# ANGEL_II_Type_III_ver2.net
KiCad netlist of a schematic drawn in EAGLE
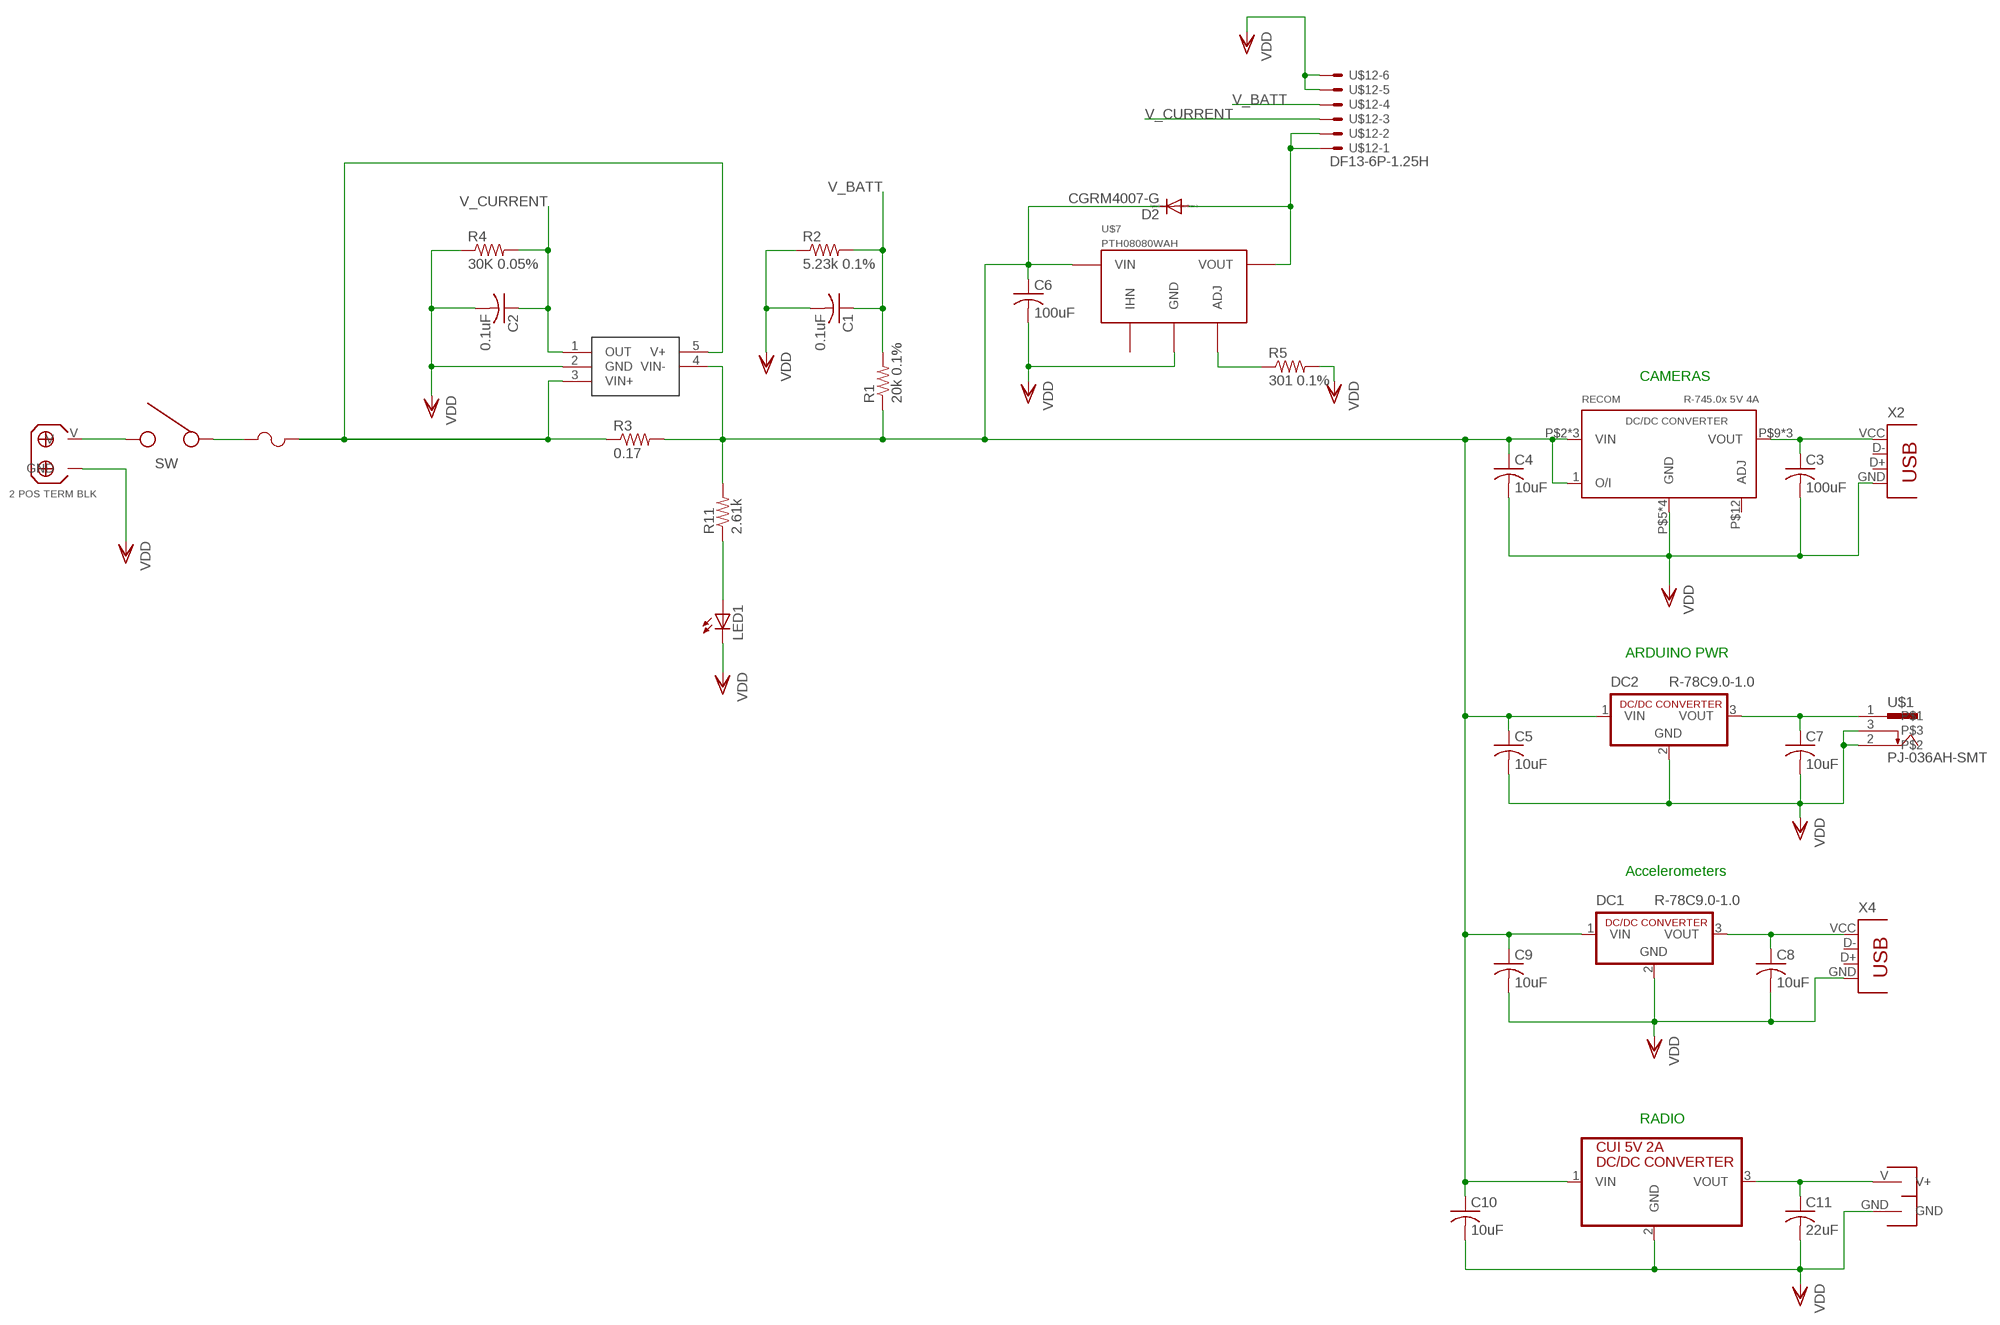
[diagram p0: schematic, sheet 1]

(export (version "E")
  (design (tool "Eeschema 10.0.6"))
  (components
    (comp (ref "C1")
      (value "0.1uF")
      (footprint "eagle-import:C0603")
      (libsource (lib "eagle-import") (part "C-USC0603"))
    )
    (comp (ref "C2")
      (value "0.1uF")
      (footprint "eagle-import:C0603")
      (libsource (lib "eagle-import") (part "C-USC0603"))
    )
    (comp (ref "C3")
      (value "100uF")
      (footprint "eagle-import:C1210")
      (libsource (lib "eagle-import") (part "C-USC1210"))
    )
    (comp (ref "C4")
      (value "10uF")
      (footprint "eagle-import:C1206")
      (libsource (lib "eagle-import") (part "C-USC1206"))
    )
    (comp (ref "C5")
      (value "10uF")
      (footprint "eagle-import:C1206")
      (libsource (lib "eagle-import") (part "C-USC1206"))
    )
    (comp (ref "C6")
      (value "100uF")
      (footprint "eagle-import:C1210")
      (libsource (lib "eagle-import") (part "C-USC1210"))
    )
    (comp (ref "C7")
      (value "10uF")
      (footprint "eagle-import:C1206")
      (libsource (lib "eagle-import") (part "C-USC1206"))
    )
    (comp (ref "C8")
      (value "10uF")
      (footprint "eagle-import:C1206")
      (libsource (lib "eagle-import") (part "C-USC1206"))
    )
    (comp (ref "C9")
      (value "10uF")
      (footprint "eagle-import:C1206")
      (libsource (lib "eagle-import") (part "C-USC1206"))
    )
    (comp (ref "C10")
      (value "10uF")
      (footprint "eagle-import:C1206")
      (libsource (lib "eagle-import") (part "C-USC1206"))
    )
    (comp (ref "C11")
      (value "22uF")
      (footprint "eagle-import:C1210")
      (libsource (lib "eagle-import") (part "C-USC1210"))
    )
    (comp (ref "D2")
      (value "CGRM4007-G")
      (footprint "eagle-import:SOD-123_MINI-SMA")
      (libsource (lib "eagle-import") (part "CGRM400-G7"))
    )
    (comp (ref "DC1")
      (value "R-78C9.0-1.0")
      (footprint "eagle-import:SIP3")
      (libsource (lib "eagle-import") (part "R-78C-1.09.0"))
    )
    (comp (ref "DC2")
      (value "R-78C9.0-1.0")
      (footprint "eagle-import:SIP3")
      (libsource (lib "eagle-import") (part "R-78C-1.09.0"))
    )
    (comp (ref "LED1")
      (value "LEDCHIPLED_0603")
      (footprint "eagle-import:CHIPLED_0603")
      (libsource (lib "eagle-import") (part "LEDCHIPLED_0603"))
    )
    (comp (ref "R1")
      (value "20k 0.1%")
      (footprint "eagle-import:R0603")
      (libsource (lib "eagle-import") (part "R-US_R0603"))
    )
    (comp (ref "R2")
      (value "5.23k 0.1%")
      (footprint "eagle-import:R0805")
      (libsource (lib "eagle-import") (part "R-US_R0805"))
    )
    (comp (ref "R3")
      (value "0.17")
      (footprint "eagle-import:R2512")
      (libsource (lib "eagle-import") (part "R-US_R2512"))
    )
    (comp (ref "R4")
      (value "30K 0.05%")
      (footprint "eagle-import:R0603")
      (libsource (lib "eagle-import") (part "R-US_R0603"))
    )
    (comp (ref "R5")
      (value "301 0.1%")
      (footprint "eagle-import:R0805")
      (libsource (lib "eagle-import") (part "R-US_R0805"))
    )
    (comp (ref "R11")
      (value "2.61k")
      (footprint "eagle-import:R0805")
      (libsource (lib "eagle-import") (part "R-US_R0805"))
    )
    (comp (ref "U$1")
      (value "PJ-036AH-SMT")
      (footprint "eagle-import:SMT_DC_POWERJACK")
      (libsource (lib "eagle-import") (part "PJ-036AH-SMT"))
    )
    (comp (ref "U$2")
      (value "INA169")
      (footprint "eagle-import:SOT23-5")
      (libsource (lib "eagle-import") (part "INA169"))
    )
    (comp (ref "U$5")
      (value "CUI_DCDC_5V2A")
      (footprint "eagle-import:CUI_V200_DCDC")
      (libsource (lib "eagle-import") (part "CUI_DCDC_5V2A"))
    )
    (comp (ref "U$6")
      (value "SPST_ROCKER_SW")
      (footprint "eagle-import:ROCKER_SW_SPST")
      (libsource (lib "eagle-import") (part "SPST_ROCKER_SW"))
    )
    (comp (ref "U$7")
      (value "PTH08080WAH")
      (footprint "eagle-import:PTH08080W_TH")
      (libsource (lib "eagle-import") (part "PTH08080WAH"))
    )
    (comp (ref "U$9")
      (value "MOLEX_2POS_HEADRE_TB")
      (footprint "eagle-import:TERM_BLK_HDR_2POS_VERT_3P5MM")
      (libsource (lib "eagle-import") (part "MOLEX_2POS_HEADRE_TB"))
    )
    (comp (ref "U$10")
      (value "2POS_TB_3.81MM")
      (footprint "eagle-import:2POS_TB_3P81MM")
      (libsource (lib "eagle-import") (part "2POS_TB_3.81MM"))
    )
    (comp (ref "U$11")
      (value "LITTLEFUSE_1206SMT")
      (footprint "eagle-import:LITTLEFUSE_SMT")
      (libsource (lib "eagle-import") (part "LITTLEFUSE_1206SMT"))
    )
    (comp (ref "U$12")
      (value "DF13-6P-1.25H")
      (footprint "eagle-import:DF13A-6P-1.25H")
      (libsource (lib "eagle-import") (part "DF13-6P-1.25?H"))
    )
    (comp (ref "U$13")
      (value "RECOM_R745_5V4A_DCDC")
      (footprint "eagle-import:12SIP_PIN")
      (libsource (lib "eagle-import") (part "RECOM_R745_5V4A_DCDC"))
    )
    (comp (ref "X2")
      (value "87583-2010BLF")
      (footprint "eagle-import:USB-A_87583-2010BLF")
      (libsource (lib "eagle-import") (part "87583-2010BLF"))
    )
    (comp (ref "X4")
      (value "87583-2010BLF")
      (footprint "eagle-import:USB-A_87583-2010BLF")
      (libsource (lib "eagle-import") (part "87583-2010BLF"))
    )
  )
  (nets
    (net (code "1") (name "/V_BATT") (class "Default")
      (node (ref "C1") (pin "1") (pinfunction "1_1") (pintype "passive"))
      (node (ref "R1") (pin "2") (pinfunction "2_2") (pintype "passive"))
      (node (ref "R2") (pin "2") (pinfunction "2_2") (pintype "passive"))
      (node (ref "U$12") (pin "4") (pinfunction "S_4") (pintype "passive"))
    )
    (net (code "2") (name "/V_CURRENT") (class "Default")
      (node (ref "C2") (pin "1") (pinfunction "1_1") (pintype "passive"))
      (node (ref "R4") (pin "2") (pinfunction "2_2") (pintype "passive"))
      (node (ref "U$12") (pin "3") (pinfunction "S_3") (pintype "passive"))
      (node (ref "U$2") (pin "1") (pinfunction "OUT_1") (pintype "bidirectional"))
    )
    (net (code "3") (name "Net-(DC1-VIN)") (class "Default")
      (node (ref "C10") (pin "1") (pinfunction "1_1") (pintype "passive"))
      (node (ref "C4") (pin "1") (pinfunction "1_1") (pintype "passive"))
      (node (ref "C5") (pin "1") (pinfunction "1_1") (pintype "passive"))
      (node (ref "C6") (pin "1") (pinfunction "1_1") (pintype "passive"))
      (node (ref "C9") (pin "1") (pinfunction "1_1") (pintype "passive"))
      (node (ref "D2") (pin "C") (pinfunction "C_C") (pintype "passive"))
      (node (ref "DC1") (pin "1") (pinfunction "VIN_1") (pintype "passive"))
      (node (ref "DC2") (pin "1") (pinfunction "VIN_1") (pintype "passive"))
      (node (ref "R1") (pin "1") (pinfunction "1_1") (pintype "passive"))
      (node (ref "R11") (pin "2") (pinfunction "2_2") (pintype "passive"))
      (node (ref "R3") (pin "2") (pinfunction "2_2") (pintype "passive"))
      (node (ref "U$13") (pin "1") (pinfunction "O/I_1") (pintype "bidirectional"))
      (node (ref "U$13") (pin "P$2") (pinfunction "VIN_P$2") (pintype "bidirectional"))
      (node (ref "U$13") (pin "P$3") (pinfunction "VIN_P$3") (pintype "bidirectional"))
      (node (ref "U$13") (pin "P$4") (pinfunction "VIN_P$4") (pintype "bidirectional"))
      (node (ref "U$2") (pin "4") (pinfunction "VIN-_4") (pintype "bidirectional"))
      (node (ref "U$5") (pin "1") (pinfunction "VIN_1") (pintype "bidirectional"))
      (node (ref "U$7") (pin "1") (pinfunction "VIN_1") (pintype "power_in"))
    )
    (net (code "4") (name "Net-(DC1-VOUT)") (class "Default")
      (node (ref "C8") (pin "1") (pinfunction "1_1") (pintype "passive"))
      (node (ref "DC1") (pin "3") (pinfunction "VOUT_3") (pintype "passive"))
      (node (ref "X4") (pin "VCC") (pinfunction "1_VCC") (pintype "passive"))
    )
    (net (code "5") (name "Net-(DC2-VOUT)") (class "Default")
      (node (ref "C7") (pin "1") (pinfunction "1_1") (pintype "passive"))
      (node (ref "DC2") (pin "3") (pinfunction "VOUT_3") (pintype "passive"))
      (node (ref "U$1") (pin "1") (pinfunction "P$1_1") (pintype "bidirectional"))
    )
    (net (code "6") (name "Net-(LED1-PadA)") (class "Default")
      (node (ref "LED1") (pin "A") (pinfunction "A_A") (pintype "passive"))
      (node (ref "R11") (pin "1") (pinfunction "1_1") (pintype "passive"))
    )
    (net (code "7") (name "Net-(U$5-VOUT)") (class "Default")
      (node (ref "C11") (pin "1") (pinfunction "1_1") (pintype "passive"))
      (node (ref "U$5") (pin "3") (pinfunction "VOUT_3") (pintype "bidirectional"))
      (node (ref "U$9") (pin "V") (pinfunction "V+_V") (pintype "bidirectional"))
    )
    (net (code "8") (name "Net-(U$6-1)") (class "Default")
      (node (ref "U$10") (pin "V") (pinfunction "V_V") (pintype "bidirectional"))
      (node (ref "U$6") (pin "P$1") (pinfunction "1_P$1") (pintype "bidirectional"))
    )
    (net (code "9") (name "Net-(U$7-ADJ)") (class "Default")
      (node (ref "R5") (pin "1") (pinfunction "1_1") (pintype "passive"))
      (node (ref "U$7") (pin "4") (pinfunction "ADJ_4") (pintype "bidirectional"))
    )
    (net (code "10") (name "Net-(U$11-P$2)") (class "Default")
      (node (ref "R3") (pin "1") (pinfunction "1_1") (pintype "passive"))
      (node (ref "U$11") (pin "P$3") (pinfunction "P$2_P$3") (pintype "bidirectional"))
      (node (ref "U$2") (pin "3") (pinfunction "VIN+_3") (pintype "bidirectional"))
      (node (ref "U$2") (pin "5") (pinfunction "V+_5") (pintype "bidirectional"))
    )
    (net (code "11") (name "Net-(U$11-PadP$1)") (class "Default")
      (node (ref "U$11") (pin "P$1") (pinfunction "P$1_P$1") (pintype "bidirectional"))
      (node (ref "U$6") (pin "P$2") (pinfunction "P$2_P$2") (pintype "bidirectional"))
    )
    (net (code "12") (name "Net-(U$12A-S)") (class "Default")
      (node (ref "D2") (pin "A") (pinfunction "A_A") (pintype "passive"))
      (node (ref "U$12") (pin "1") (pinfunction "S_1") (pintype "passive"))
      (node (ref "U$12") (pin "2") (pinfunction "S_2") (pintype "passive"))
      (node (ref "U$7") (pin "3") (pinfunction "VOUT_3") (pintype "power_in"))
    )
    (net (code "13") (name "Net-(X2-1)") (class "Default")
      (node (ref "C3") (pin "1") (pinfunction "1_1") (pintype "passive"))
      (node (ref "U$13") (pin "P$10") (pinfunction "VOUT_P$10") (pintype "bidirectional"))
      (node (ref "U$13") (pin "P$11") (pinfunction "VOUT_P$11") (pintype "bidirectional"))
      (node (ref "U$13") (pin "P$9") (pinfunction "VOUT_P$9") (pintype "bidirectional"))
      (node (ref "X2") (pin "VCC") (pinfunction "1_VCC") (pintype "passive"))
    )
    (net (code "14") (name "VDD") (class "Default")
      (node (ref "C1") (pin "2") (pinfunction "2_2") (pintype "passive"))
      (node (ref "C10") (pin "2") (pinfunction "2_2") (pintype "passive"))
      (node (ref "C11") (pin "2") (pinfunction "2_2") (pintype "passive"))
      (node (ref "C2") (pin "2") (pinfunction "2_2") (pintype "passive"))
      (node (ref "C3") (pin "2") (pinfunction "2_2") (pintype "passive"))
      (node (ref "C4") (pin "2") (pinfunction "2_2") (pintype "passive"))
      (node (ref "C5") (pin "2") (pinfunction "2_2") (pintype "passive"))
      (node (ref "C6") (pin "2") (pinfunction "2_2") (pintype "passive"))
      (node (ref "C7") (pin "2") (pinfunction "2_2") (pintype "passive"))
      (node (ref "C8") (pin "2") (pinfunction "2_2") (pintype "passive"))
      (node (ref "C9") (pin "2") (pinfunction "2_2") (pintype "passive"))
      (node (ref "DC1") (pin "2") (pinfunction "GND_2") (pintype "passive"))
      (node (ref "DC2") (pin "2") (pinfunction "GND_2") (pintype "passive"))
      (node (ref "LED1") (pin "C") (pinfunction "C_C") (pintype "passive"))
      (node (ref "R2") (pin "1") (pinfunction "1_1") (pintype "passive"))
      (node (ref "R4") (pin "1") (pinfunction "1_1") (pintype "passive"))
      (node (ref "R5") (pin "2") (pinfunction "2_2") (pintype "passive"))
      (node (ref "U$1") (pin "2") (pinfunction "P$2_2") (pintype "bidirectional"))
      (node (ref "U$1") (pin "3") (pinfunction "P$3_3") (pintype "bidirectional"))
      (node (ref "U$10") (pin "GND") (pinfunction "GND_GND") (pintype "bidirectional"))
      (node (ref "U$12") (pin "5") (pinfunction "S_5") (pintype "passive"))
      (node (ref "U$12") (pin "6") (pinfunction "S_6") (pintype "passive"))
      (node (ref "U$13") (pin "P$5") (pinfunction "GND_P$5") (pintype "bidirectional"))
      (node (ref "U$13") (pin "P$6") (pinfunction "GND_P$6") (pintype "bidirectional"))
      (node (ref "U$13") (pin "P$7") (pinfunction "GND_P$7") (pintype "bidirectional"))
      (node (ref "U$13") (pin "P$8") (pinfunction "GND_P$8") (pintype "bidirectional"))
      (node (ref "U$2") (pin "2") (pinfunction "GND_2") (pintype "bidirectional"))
      (node (ref "U$5") (pin "2") (pinfunction "GND_2") (pintype "bidirectional"))
      (node (ref "U$7") (pin "2") (pinfunction "GND_2") (pintype "power_in"))
      (node (ref "U$9") (pin "GND") (pinfunction "GND_GND") (pintype "bidirectional"))
      (node (ref "X2") (pin "GND") (pinfunction "4_GND") (pintype "passive"))
      (node (ref "X4") (pin "GND") (pinfunction "4_GND") (pintype "passive"))
    )
    (net (code "15") (name "unconnected-(U$7-IHN-Pad5)") (class "Default")
      (node (ref "U$7") (pin "5") (pinfunction "IHN_5") (pintype "bidirectional"))
    )
    (net (code "16") (name "unconnected-(U$13-ADJ-PadP$12)") (class "Default")
      (node (ref "U$13") (pin "P$12") (pinfunction "ADJ_P$12") (pintype "bidirectional"))
    )
    (net (code "17") (name "unconnected-(X2-2-PadD-)") (class "Default")
      (node (ref "X2") (pin "D-") (pinfunction "2_D-") (pintype "passive"))
    )
    (net (code "18") (name "unconnected-(X2-3-PadD+)") (class "Default")
      (node (ref "X2") (pin "D+") (pinfunction "3_D+") (pintype "passive"))
    )
    (net (code "19") (name "unconnected-(X4-2-PadD-)") (class "Default")
      (node (ref "X4") (pin "D-") (pinfunction "2_D-") (pintype "passive"))
    )
    (net (code "20") (name "unconnected-(X4-3-PadD+)") (class "Default")
      (node (ref "X4") (pin "D+") (pinfunction "3_D+") (pintype "passive"))
    )
  )
)
